# suns_wifi_egse_esp8266.net
KiCad netlist of a schematic drawn in Altium Designer
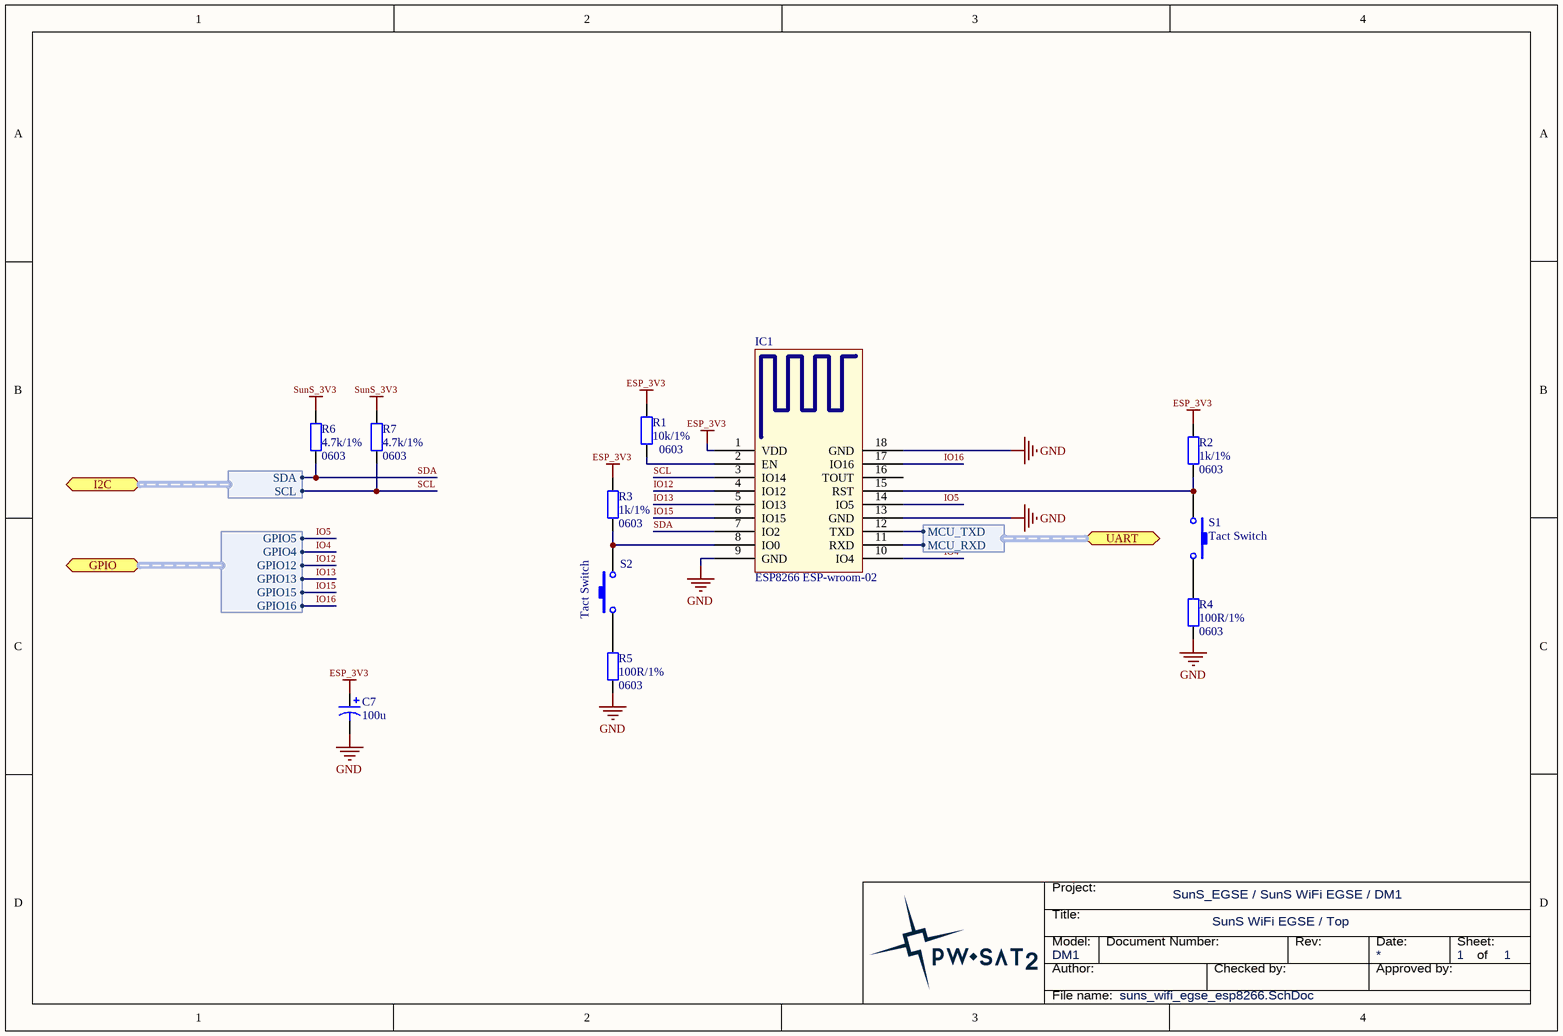
[diagram p0: suns_wifi_egse_esp8266.SchDoc]

(export (version "E")
  (design (tool "Eeschema 10.0.6"))
  (components
    (comp (ref "C7")
      (value "100u")
      (footprint "CAP_ELEC_6.3x4.2")
      (description "Polarized Capacitor")
      (libsource (lib "WSN") (part "Cap Pol"))
    )
    (comp (ref "IC1")
      (value "ESP8266 ESP-wroom-02")
      (footprint "ESP8266 ESP-wroom-02")
      (libsource (lib "microcircuits") (part "ESP8266 ESP-wroom-02"))
    )
    (comp (ref "R1")
      (value "10k/1%")
      (footprint "SMD_Resistor_0603")
      (description "1k/1% Vishay CRCW 0603 Resistor. 100mW, 100ppm, 75V.")
      (fields
        (field (name "MANUFACTURER") "Vishay")
        (field (name "MANUFACTURERPARTNUMBER") "CRCW06031K00FKxxxx")
        (field (name "PACKAGE") "0603")
      )
      (libsource (lib "resistors") (part "CRCW06031K00FKxxxx"))
    )
    (comp (ref "R2")
      (value "1k/1%")
      (footprint "SMD_Resistor_0603")
      (description "1k/1% Vishay CRCW 0603 Resistor. 100mW, 100ppm, 75V.")
      (fields
        (field (name "MANUFACTURER") "Vishay")
        (field (name "MANUFACTURERPARTNUMBER") "CRCW06031K00FKxxxx")
        (field (name "PACKAGE") "0603")
      )
      (libsource (lib "") (part "CRCW06031K00FKxxxx_1"))
    )
    (comp (ref "R3")
      (value "1k/1%")
      (footprint "SMD_Resistor_0603")
      (description "1k/1% Vishay CRCW 0603 Resistor. 100mW, 100ppm, 75V.")
      (fields
        (field (name "MANUFACTURER") "Vishay")
        (field (name "MANUFACTURERPARTNUMBER") "CRCW06031K00FKxxxx")
        (field (name "PACKAGE") "0603")
      )
      (libsource (lib "resistors") (part "CRCW06031K00FKxxxx"))
    )
    (comp (ref "R4")
      (value "100R/1%")
      (footprint "SMD_Resistor_0603")
      (description "1k/1% Vishay CRCW 0603 Resistor. 100mW, 100ppm, 75V.")
      (fields
        (field (name "MANUFACTURER") "Vishay")
        (field (name "MANUFACTURERPARTNUMBER") "CRCW06031K00FKxxxx")
        (field (name "PACKAGE") "0603")
      )
      (libsource (lib "") (part "CRCW06031K00FKxxxx_1"))
    )
    (comp (ref "R5")
      (value "100R/1%")
      (footprint "SMD_Resistor_0603")
      (description "1k/1% Vishay CRCW 0603 Resistor. 100mW, 100ppm, 75V.")
      (fields
        (field (name "MANUFACTURER") "Vishay")
        (field (name "MANUFACTURERPARTNUMBER") "CRCW06031K00FKxxxx")
        (field (name "PACKAGE") "0603")
      )
      (libsource (lib "resistors") (part "CRCW06031K00FKxxxx"))
    )
    (comp (ref "R6")
      (value "4.7k/1%")
      (footprint "SMD_Resistor_0603")
      (description "4.7k/1% Vishay CRCW 0603 Resistor. 100mW, 100ppm, 75V.")
      (fields
        (field (name "MANUFACTURER") "Vishay")
        (field (name "MANUFACTUERPARTNUMBER") "CRCW06034K70FKxxxx")
        (field (name "PACKAGE") "0603")
      )
      (libsource (lib "resistors") (part "CRCW06034K70FKxxxx"))
    )
    (comp (ref "R7")
      (value "4.7k/1%")
      (footprint "SMD_Resistor_0603")
      (description "4.7k/1% Vishay CRCW 0603 Resistor. 100mW, 100ppm, 75V.")
      (fields
        (field (name "MANUFACTURER") "Vishay")
        (field (name "MANUFACTUERPARTNUMBER") "CRCW06034K70FKxxxx")
        (field (name "PACKAGE") "0603")
      )
      (libsource (lib "resistors") (part "CRCW06034K70FKxxxx"))
    )
    (comp (ref "S1")
      (value "Tact Switch")
      (footprint "Tact Switch 3x6")
      (libsource (lib "switches") (part "TactSwitch"))
    )
    (comp (ref "S2")
      (value "Tact Switch")
      (footprint "Tact Switch 3x6")
      (libsource (lib "switches") (part "TactSwitch"))
    )
  )
  (nets
    (net (code "4") (name "/IO4") (class "Default")
      (node (ref "IC1") (pin "10") (pinfunction "IO4_10") (pintype "passive"))
    )
    (net (code "5") (name "/IO5") (class "Default")
      (node (ref "IC1") (pin "14") (pinfunction "IO5_14") (pintype "passive"))
    )
    (net (code "6") (name "/IO12") (class "Default")
      (node (ref "IC1") (pin "4") (pinfunction "IO12_4") (pintype "passive"))
    )
    (net (code "7") (name "/IO13") (class "Default")
      (node (ref "IC1") (pin "5") (pinfunction "IO13_5") (pintype "passive"))
    )
    (net (code "8") (name "/IO15") (class "Default")
      (node (ref "IC1") (pin "6") (pinfunction "IO15_6") (pintype "passive"))
    )
    (net (code "9") (name "/IO16") (class "Default")
      (node (ref "IC1") (pin "17") (pinfunction "IO16_17") (pintype "passive"))
    )
    (net (code "10") (name "/MCU_RXD") (class "Default")
      (node (ref "IC1") (pin "11") (pinfunction "RXD_11") (pintype "passive"))
    )
    (net (code "11") (name "/MCU_TXD") (class "Default")
      (node (ref "IC1") (pin "12") (pinfunction "TXD_12") (pintype "passive"))
    )
    (net (code "12") (name "/SCL") (class "Default")
      (node (ref "IC1") (pin "3") (pinfunction "IO14_3") (pintype "passive"))
      (node (ref "R7") (pin "2") (pinfunction "2_2") (pintype "passive"))
    )
    (net (code "13") (name "/SDA") (class "Default")
      (node (ref "IC1") (pin "7") (pinfunction "IO2_7") (pintype "passive"))
      (node (ref "R6") (pin "2") (pinfunction "2_2") (pintype "passive"))
    )
    (net (code "17") (name "ESP_3V3") (class "Default")
      (node (ref "C7") (pin "1") (pinfunction "1_1") (pintype "passive"))
      (node (ref "IC1") (pin "1") (pinfunction "VDD_1") (pintype "passive"))
      (node (ref "R1") (pin "2") (pinfunction "2_2") (pintype "passive"))
      (node (ref "R2") (pin "2") (pinfunction "2_2") (pintype "passive"))
      (node (ref "R3") (pin "2") (pinfunction "2_2") (pintype "passive"))
    )
    (net (code "18") (name "GND") (class "Default")
      (node (ref "C7") (pin "2") (pinfunction "2_2") (pintype "passive"))
      (node (ref "IC1") (pin "13") (pinfunction "GND_13") (pintype "passive"))
      (node (ref "IC1") (pin "18") (pinfunction "GND_18") (pintype "passive"))
      (node (ref "IC1") (pin "9") (pinfunction "GND_9") (pintype "passive"))
      (node (ref "R4") (pin "1") (pinfunction "1_1") (pintype "passive"))
      (node (ref "R5") (pin "1") (pinfunction "1_1") (pintype "passive"))
    )
    (net (code "19") (name "Net-(IC1-EN)") (class "Default")
      (node (ref "IC1") (pin "2") (pinfunction "EN_2") (pintype "passive"))
      (node (ref "R1") (pin "1") (pinfunction "1_1") (pintype "passive"))
    )
    (net (code "20") (name "Net-(IC1-IO0)") (class "Default")
      (node (ref "IC1") (pin "8") (pinfunction "IO0_8") (pintype "passive"))
      (node (ref "R3") (pin "1") (pinfunction "1_1") (pintype "passive"))
      (node (ref "S2") (pin "2") (pinfunction "2_2") (pintype "passive"))
    )
    (net (code "21") (name "Net-(IC1-RST)") (class "Default")
      (node (ref "IC1") (pin "15") (pinfunction "RST_15") (pintype "passive"))
      (node (ref "R2") (pin "1") (pinfunction "1_1") (pintype "passive"))
      (node (ref "S1") (pin "2") (pinfunction "2_2") (pintype "passive"))
    )
    (net (code "22") (name "Net-(R4-Pad2)") (class "Default")
      (node (ref "R4") (pin "2") (pinfunction "2_2") (pintype "passive"))
      (node (ref "S1") (pin "1") (pinfunction "1_1") (pintype "passive"))
    )
    (net (code "23") (name "Net-(R5-Pad2)") (class "Default")
      (node (ref "R5") (pin "2") (pinfunction "2_2") (pintype "passive"))
      (node (ref "S2") (pin "1") (pinfunction "1_1") (pintype "passive"))
    )
    (net (code "24") (name "SunS_3V3") (class "Default")
      (node (ref "R6") (pin "1") (pinfunction "1_1") (pintype "passive"))
      (node (ref "R7") (pin "1") (pinfunction "1_1") (pintype "passive"))
    )
    (net (code "25") (name "unconnected-(IC1-TOUT-Pad16)") (class "Default")
      (node (ref "IC1") (pin "16") (pinfunction "TOUT_16") (pintype "passive"))
    )
  )
)
